# board.net
KiCad netlist of a schematic drawn in EAGLE
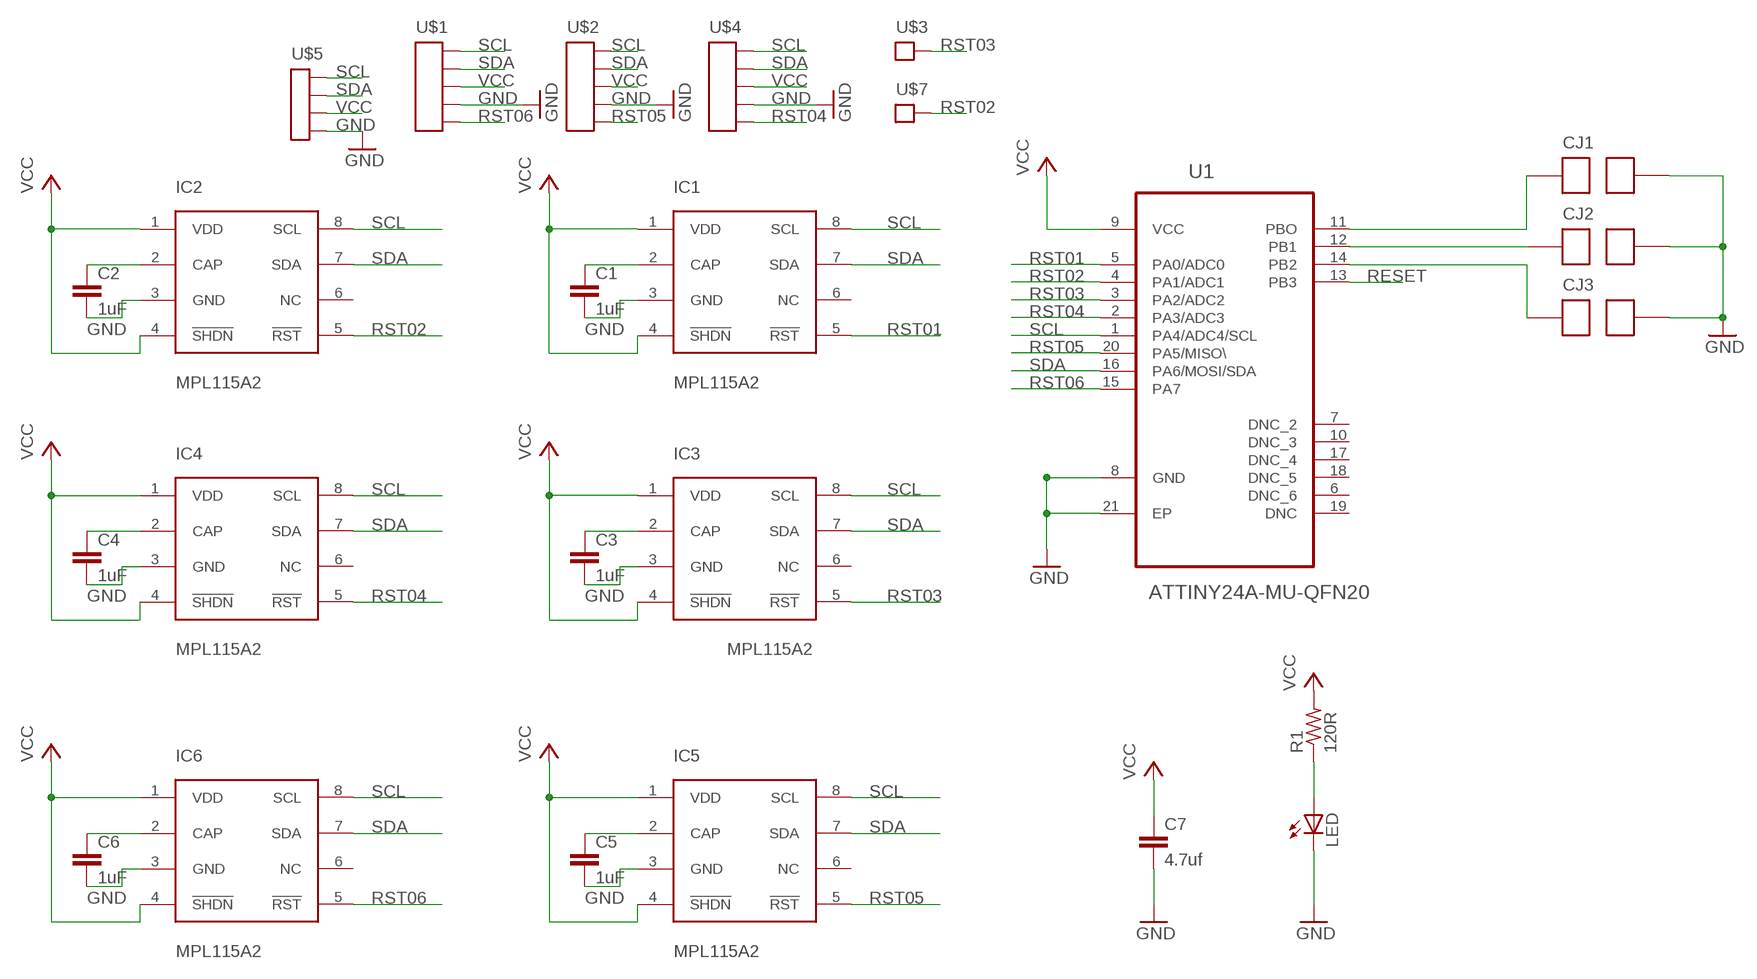
[diagram p0: schematic, sheet 1]

(export (version "E")
  (design (tool "Eeschema 10.0.6"))
  (components
    (comp (ref "C1")
      (value "1uF")
      (footprint "eagle-import:C0402")
      (libsource (lib "eagle-import") (part "C-EUC0402"))
    )
    (comp (ref "C2")
      (value "1uF")
      (footprint "eagle-import:C0402")
      (libsource (lib "eagle-import") (part "C-EUC0402"))
    )
    (comp (ref "C3")
      (value "1uF")
      (footprint "eagle-import:C0402")
      (libsource (lib "eagle-import") (part "C-EUC0402"))
    )
    (comp (ref "C4")
      (value "1uF")
      (footprint "eagle-import:C0402")
      (libsource (lib "eagle-import") (part "C-EUC0402"))
    )
    (comp (ref "C5")
      (value "1uF")
      (footprint "eagle-import:C0402")
      (libsource (lib "eagle-import") (part "C-EUC0402"))
    )
    (comp (ref "C6")
      (value "1uF")
      (footprint "eagle-import:C0402")
      (libsource (lib "eagle-import") (part "C-EUC0402"))
    )
    (comp (ref "C7")
      (value "4.7uf")
      (footprint "eagle-import:C0402")
      (libsource (lib "eagle-import") (part "C-EUC0402"))
    )
    (comp (ref "CJ1")
      (value "2_P")
      (footprint "eagle-import:2_P")
      (libsource (lib "eagle-import") (part "2_P"))
    )
    (comp (ref "CJ2")
      (value "2_P")
      (footprint "eagle-import:2_P")
      (libsource (lib "eagle-import") (part "2_P"))
    )
    (comp (ref "CJ3")
      (value "2_P")
      (footprint "eagle-import:2_P")
      (libsource (lib "eagle-import") (part "2_P"))
    )
    (comp (ref "IC1")
      (value "MPL115A2")
      (footprint "eagle-import:MPL115A2")
      (libsource (lib "eagle-import") (part "MPL115A2"))
    )
    (comp (ref "IC2")
      (value "MPL115A2")
      (footprint "eagle-import:MPL115A2")
      (libsource (lib "eagle-import") (part "MPL115A2"))
    )
    (comp (ref "IC3")
      (value "MPL115A2")
      (footprint "eagle-import:MPL115A2")
      (libsource (lib "eagle-import") (part "MPL115A2"))
    )
    (comp (ref "IC4")
      (value "MPL115A2")
      (footprint "eagle-import:MPL115A2")
      (libsource (lib "eagle-import") (part "MPL115A2"))
    )
    (comp (ref "IC5")
      (value "MPL115A2")
      (footprint "eagle-import:MPL115A2")
      (libsource (lib "eagle-import") (part "MPL115A2"))
    )
    (comp (ref "IC6")
      (value "MPL115A2")
      (footprint "eagle-import:MPL115A2")
      (libsource (lib "eagle-import") (part "MPL115A2"))
    )
    (comp (ref "LED")
      (value "LEDSML0603")
      (footprint "eagle-import:SML0603")
      (libsource (lib "eagle-import") (part "LEDSML0603"))
    )
    (comp (ref "R1")
      (value "120R")
      (footprint "eagle-import:R0402")
      (libsource (lib "eagle-import") (part "R-US_R0402"))
    )
    (comp (ref "U$1")
      (value "5_PIN_CON")
      (footprint "eagle-import:5_PIN_CON")
      (libsource (lib "eagle-import") (part "5_PIN_CON"))
    )
    (comp (ref "U$2")
      (value "5_PIN_CON")
      (footprint "eagle-import:5_PIN_CON")
      (libsource (lib "eagle-import") (part "5_PIN_CON"))
    )
    (comp (ref "U$3")
      (value "1_PIN_CON")
      (footprint "eagle-import:1_PIN_CON")
      (libsource (lib "eagle-import") (part "1_PIN_CON"))
    )
    (comp (ref "U$4")
      (value "5_PIN_CON")
      (footprint "eagle-import:5_PIN_CON")
      (libsource (lib "eagle-import") (part "5_PIN_CON"))
    )
    (comp (ref "U$5")
      (value "4_PIN_CON")
      (footprint "eagle-import:4_PIN_CON")
      (libsource (lib "eagle-import") (part "4_PIN_CON"))
    )
    (comp (ref "U$7")
      (value "1_PIN_CON")
      (footprint "eagle-import:1_PIN_CON")
      (libsource (lib "eagle-import") (part "1_PIN_CON"))
    )
    (comp (ref "U1")
      (value "ATTINY24A-MU-QFN20")
      (footprint "eagle-import:QFN50P400X400X80-21N")
      (fields (field (name "MPN") "ATTINY24A-MU"))
      (libsource (lib "eagle-import") (part "ATTINY24A-MU"))
    )
  )
  (nets
    (net (code "1") (name "/RESET") (class "Default")
      (node (ref "U1") (pin "13") (pinfunction "PB3_13") (pintype "bidirectional"))
    )
    (net (code "2") (name "/RST01") (class "Default")
      (node (ref "IC1") (pin "5") (pinfunction "~{RST}_5") (pintype "input"))
      (node (ref "U1") (pin "5") (pinfunction "PA0/ADC0_5") (pintype "bidirectional"))
    )
    (net (code "3") (name "/RST02") (class "Default")
      (node (ref "IC2") (pin "5") (pinfunction "~{RST}_5") (pintype "input"))
      (node (ref "U$7") (pin "1") (pinfunction "RTS_1") (pintype "bidirectional"))
      (node (ref "U1") (pin "4") (pinfunction "PA1/ADC1_4") (pintype "bidirectional"))
    )
    (net (code "4") (name "/RST03") (class "Default")
      (node (ref "IC3") (pin "5") (pinfunction "~{RST}_5") (pintype "input"))
      (node (ref "U$3") (pin "1") (pinfunction "RTS_1") (pintype "bidirectional"))
      (node (ref "U1") (pin "3") (pinfunction "PA2/ADC2_3") (pintype "bidirectional"))
    )
    (net (code "5") (name "/RST04") (class "Default")
      (node (ref "IC4") (pin "5") (pinfunction "~{RST}_5") (pintype "input"))
      (node (ref "U$4") (pin "5") (pinfunction "RST_5") (pintype "bidirectional"))
      (node (ref "U1") (pin "2") (pinfunction "PA3/ADC3_2") (pintype "bidirectional"))
    )
    (net (code "6") (name "/RST05") (class "Default")
      (node (ref "IC5") (pin "5") (pinfunction "~{RST}_5") (pintype "input"))
      (node (ref "U$2") (pin "5") (pinfunction "RST_5") (pintype "bidirectional"))
      (node (ref "U1") (pin "20") (pinfunction "PA5/MISO\\_20") (pintype "bidirectional"))
    )
    (net (code "7") (name "/RST06") (class "Default")
      (node (ref "IC6") (pin "5") (pinfunction "~{RST}_5") (pintype "input"))
      (node (ref "U$1") (pin "5") (pinfunction "RST_5") (pintype "bidirectional"))
      (node (ref "U1") (pin "15") (pinfunction "PA7_15") (pintype "bidirectional"))
    )
    (net (code "8") (name "/SCL") (class "Default")
      (node (ref "IC1") (pin "8") (pinfunction "SCL_8") (pintype "bidirectional"))
      (node (ref "IC2") (pin "8") (pinfunction "SCL_8") (pintype "bidirectional"))
      (node (ref "IC3") (pin "8") (pinfunction "SCL_8") (pintype "bidirectional"))
      (node (ref "IC4") (pin "8") (pinfunction "SCL_8") (pintype "bidirectional"))
      (node (ref "IC5") (pin "8") (pinfunction "SCL_8") (pintype "bidirectional"))
      (node (ref "IC6") (pin "8") (pinfunction "SCL_8") (pintype "bidirectional"))
      (node (ref "U$1") (pin "1") (pinfunction "CLK_1") (pintype "bidirectional"))
      (node (ref "U$2") (pin "1") (pinfunction "CLK_1") (pintype "bidirectional"))
      (node (ref "U$4") (pin "1") (pinfunction "CLK_1") (pintype "bidirectional"))
      (node (ref "U$5") (pin "1") (pinfunction "CLK_1") (pintype "bidirectional"))
      (node (ref "U1") (pin "1") (pinfunction "PA4/ADC4/SCL_1") (pintype "bidirectional"))
    )
    (net (code "9") (name "/SDA") (class "Default")
      (node (ref "IC1") (pin "7") (pinfunction "SDA_7") (pintype "bidirectional"))
      (node (ref "IC2") (pin "7") (pinfunction "SDA_7") (pintype "bidirectional"))
      (node (ref "IC3") (pin "7") (pinfunction "SDA_7") (pintype "bidirectional"))
      (node (ref "IC4") (pin "7") (pinfunction "SDA_7") (pintype "bidirectional"))
      (node (ref "IC5") (pin "7") (pinfunction "SDA_7") (pintype "bidirectional"))
      (node (ref "IC6") (pin "7") (pinfunction "SDA_7") (pintype "bidirectional"))
      (node (ref "U$1") (pin "2") (pinfunction "DATA_2") (pintype "bidirectional"))
      (node (ref "U$2") (pin "2") (pinfunction "DATA_2") (pintype "bidirectional"))
      (node (ref "U$4") (pin "2") (pinfunction "DATA_2") (pintype "bidirectional"))
      (node (ref "U$5") (pin "2") (pinfunction "DATA_2") (pintype "bidirectional"))
      (node (ref "U1") (pin "16") (pinfunction "PA6/MOSI/SDA_16") (pintype "bidirectional"))
    )
    (net (code "10") (name "GND") (class "Default")
      (node (ref "C1") (pin "2") (pinfunction "2_2") (pintype "passive"))
      (node (ref "C2") (pin "2") (pinfunction "2_2") (pintype "passive"))
      (node (ref "C3") (pin "2") (pinfunction "2_2") (pintype "passive"))
      (node (ref "C4") (pin "2") (pinfunction "2_2") (pintype "passive"))
      (node (ref "C5") (pin "2") (pinfunction "2_2") (pintype "passive"))
      (node (ref "C6") (pin "2") (pinfunction "2_2") (pintype "passive"))
      (node (ref "C7") (pin "2") (pinfunction "2_2") (pintype "passive"))
      (node (ref "CJ1") (pin "P$2") (pinfunction "P$2_P$2") (pintype "bidirectional"))
      (node (ref "CJ2") (pin "P$2") (pinfunction "P$2_P$2") (pintype "bidirectional"))
      (node (ref "CJ3") (pin "P$2") (pinfunction "P$2_P$2") (pintype "bidirectional"))
      (node (ref "IC1") (pin "3") (pinfunction "GND_3") (pintype "power_in"))
      (node (ref "IC2") (pin "3") (pinfunction "GND_3") (pintype "power_in"))
      (node (ref "IC3") (pin "3") (pinfunction "GND_3") (pintype "power_in"))
      (node (ref "IC4") (pin "3") (pinfunction "GND_3") (pintype "power_in"))
      (node (ref "IC5") (pin "3") (pinfunction "GND_3") (pintype "power_in"))
      (node (ref "IC6") (pin "3") (pinfunction "GND_3") (pintype "power_in"))
      (node (ref "LED") (pin "C") (pinfunction "C_C") (pintype "passive"))
      (node (ref "U$1") (pin "4") (pinfunction "GND_4") (pintype "bidirectional"))
      (node (ref "U$2") (pin "4") (pinfunction "GND_4") (pintype "bidirectional"))
      (node (ref "U$4") (pin "4") (pinfunction "GND_4") (pintype "bidirectional"))
      (node (ref "U$5") (pin "4") (pinfunction "GND_4") (pintype "bidirectional"))
      (node (ref "U1") (pin "21") (pinfunction "EP_21") (pintype "passive"))
      (node (ref "U1") (pin "8") (pinfunction "GND_8") (pintype "passive"))
    )
    (net (code "11") (name "Net-(IC1-CAP)") (class "Default")
      (node (ref "C1") (pin "1") (pinfunction "1_1") (pintype "passive"))
      (node (ref "IC1") (pin "2") (pinfunction "CAP_2") (pintype "bidirectional"))
    )
    (net (code "12") (name "Net-(IC2-CAP)") (class "Default")
      (node (ref "C2") (pin "1") (pinfunction "1_1") (pintype "passive"))
      (node (ref "IC2") (pin "2") (pinfunction "CAP_2") (pintype "bidirectional"))
    )
    (net (code "13") (name "Net-(IC3-CAP)") (class "Default")
      (node (ref "C3") (pin "1") (pinfunction "1_1") (pintype "passive"))
      (node (ref "IC3") (pin "2") (pinfunction "CAP_2") (pintype "bidirectional"))
    )
    (net (code "14") (name "Net-(IC4-CAP)") (class "Default")
      (node (ref "C4") (pin "1") (pinfunction "1_1") (pintype "passive"))
      (node (ref "IC4") (pin "2") (pinfunction "CAP_2") (pintype "bidirectional"))
    )
    (net (code "15") (name "Net-(IC5-CAP)") (class "Default")
      (node (ref "C5") (pin "1") (pinfunction "1_1") (pintype "passive"))
      (node (ref "IC5") (pin "2") (pinfunction "CAP_2") (pintype "bidirectional"))
    )
    (net (code "16") (name "Net-(IC6-CAP)") (class "Default")
      (node (ref "C6") (pin "1") (pinfunction "1_1") (pintype "passive"))
      (node (ref "IC6") (pin "2") (pinfunction "CAP_2") (pintype "bidirectional"))
    )
    (net (code "17") (name "Net-(LED-PadA)") (class "Default")
      (node (ref "LED") (pin "A") (pinfunction "A_A") (pintype "passive"))
      (node (ref "R1") (pin "1") (pinfunction "1_1") (pintype "passive"))
    )
    (net (code "18") (name "Net-(U1-PB1)") (class "Default")
      (node (ref "CJ2") (pin "P$1") (pinfunction "P$1_P$1") (pintype "bidirectional"))
      (node (ref "U1") (pin "12") (pinfunction "PB1_12") (pintype "bidirectional"))
    )
    (net (code "19") (name "Net-(U1-PB2)") (class "Default")
      (node (ref "CJ3") (pin "P$1") (pinfunction "P$1_P$1") (pintype "bidirectional"))
      (node (ref "U1") (pin "14") (pinfunction "PB2_14") (pintype "bidirectional"))
    )
    (net (code "20") (name "Net-(U1-PBO)") (class "Default")
      (node (ref "CJ1") (pin "P$1") (pinfunction "P$1_P$1") (pintype "bidirectional"))
      (node (ref "U1") (pin "11") (pinfunction "PBO_11") (pintype "bidirectional"))
    )
    (net (code "21") (name "VCC") (class "Default")
      (node (ref "C7") (pin "1") (pinfunction "1_1") (pintype "passive"))
      (node (ref "IC1") (pin "1") (pinfunction "VDD_1") (pintype "power_in"))
      (node (ref "IC1") (pin "4") (pinfunction "~{SHDN}_4") (pintype "input"))
      (node (ref "IC2") (pin "1") (pinfunction "VDD_1") (pintype "power_in"))
      (node (ref "IC2") (pin "4") (pinfunction "~{SHDN}_4") (pintype "input"))
      (node (ref "IC3") (pin "1") (pinfunction "VDD_1") (pintype "power_in"))
      (node (ref "IC3") (pin "4") (pinfunction "~{SHDN}_4") (pintype "input"))
      (node (ref "IC4") (pin "1") (pinfunction "VDD_1") (pintype "power_in"))
      (node (ref "IC4") (pin "4") (pinfunction "~{SHDN}_4") (pintype "input"))
      (node (ref "IC5") (pin "1") (pinfunction "VDD_1") (pintype "power_in"))
      (node (ref "IC5") (pin "4") (pinfunction "~{SHDN}_4") (pintype "input"))
      (node (ref "IC6") (pin "1") (pinfunction "VDD_1") (pintype "power_in"))
      (node (ref "IC6") (pin "4") (pinfunction "~{SHDN}_4") (pintype "input"))
      (node (ref "R1") (pin "2") (pinfunction "2_2") (pintype "passive"))
      (node (ref "U$1") (pin "3") (pinfunction "VCC_3") (pintype "bidirectional"))
      (node (ref "U$2") (pin "3") (pinfunction "VCC_3") (pintype "bidirectional"))
      (node (ref "U$4") (pin "3") (pinfunction "VCC_3") (pintype "bidirectional"))
      (node (ref "U$5") (pin "3") (pinfunction "VCC_3") (pintype "bidirectional"))
      (node (ref "U1") (pin "9") (pinfunction "VCC_9") (pintype "power_in"))
    )
    (net (code "22") (name "unconnected-(IC1-NC-Pad6)") (class "Default")
      (node (ref "IC1") (pin "6") (pinfunction "NC_6") (pintype "no_connect"))
    )
    (net (code "23") (name "unconnected-(IC2-NC-Pad6)") (class "Default")
      (node (ref "IC2") (pin "6") (pinfunction "NC_6") (pintype "no_connect"))
    )
    (net (code "24") (name "unconnected-(IC3-NC-Pad6)") (class "Default")
      (node (ref "IC3") (pin "6") (pinfunction "NC_6") (pintype "no_connect"))
    )
    (net (code "25") (name "unconnected-(IC4-NC-Pad6)") (class "Default")
      (node (ref "IC4") (pin "6") (pinfunction "NC_6") (pintype "no_connect"))
    )
    (net (code "26") (name "unconnected-(IC5-NC-Pad6)") (class "Default")
      (node (ref "IC5") (pin "6") (pinfunction "NC_6") (pintype "no_connect"))
    )
    (net (code "27") (name "unconnected-(IC6-NC-Pad6)") (class "Default")
      (node (ref "IC6") (pin "6") (pinfunction "NC_6") (pintype "no_connect"))
    )
    (net (code "28") (name "unconnected-(U1-DNC-Pad19)") (class "Default")
      (node (ref "U1") (pin "19") (pinfunction "DNC_19") (pintype "no_connect"))
    )
    (net (code "29") (name "unconnected-(U1-DNC_2-Pad7)") (class "Default")
      (node (ref "U1") (pin "7") (pinfunction "DNC_2_7") (pintype "no_connect"))
    )
    (net (code "30") (name "unconnected-(U1-DNC_3-Pad10)") (class "Default")
      (node (ref "U1") (pin "10") (pinfunction "DNC_3_10") (pintype "no_connect"))
    )
    (net (code "31") (name "unconnected-(U1-DNC_4-Pad17)") (class "Default")
      (node (ref "U1") (pin "17") (pinfunction "DNC_4_17") (pintype "no_connect"))
    )
    (net (code "32") (name "unconnected-(U1-DNC_5-Pad18)") (class "Default")
      (node (ref "U1") (pin "18") (pinfunction "DNC_5_18") (pintype "no_connect"))
    )
    (net (code "33") (name "unconnected-(U1-DNC_6-Pad6)") (class "Default")
      (node (ref "U1") (pin "6") (pinfunction "DNC_6_6") (pintype "no_connect"))
    )
  )
)
